# Solarduino.net
KiCad netlist of a schematic drawn in EAGLE
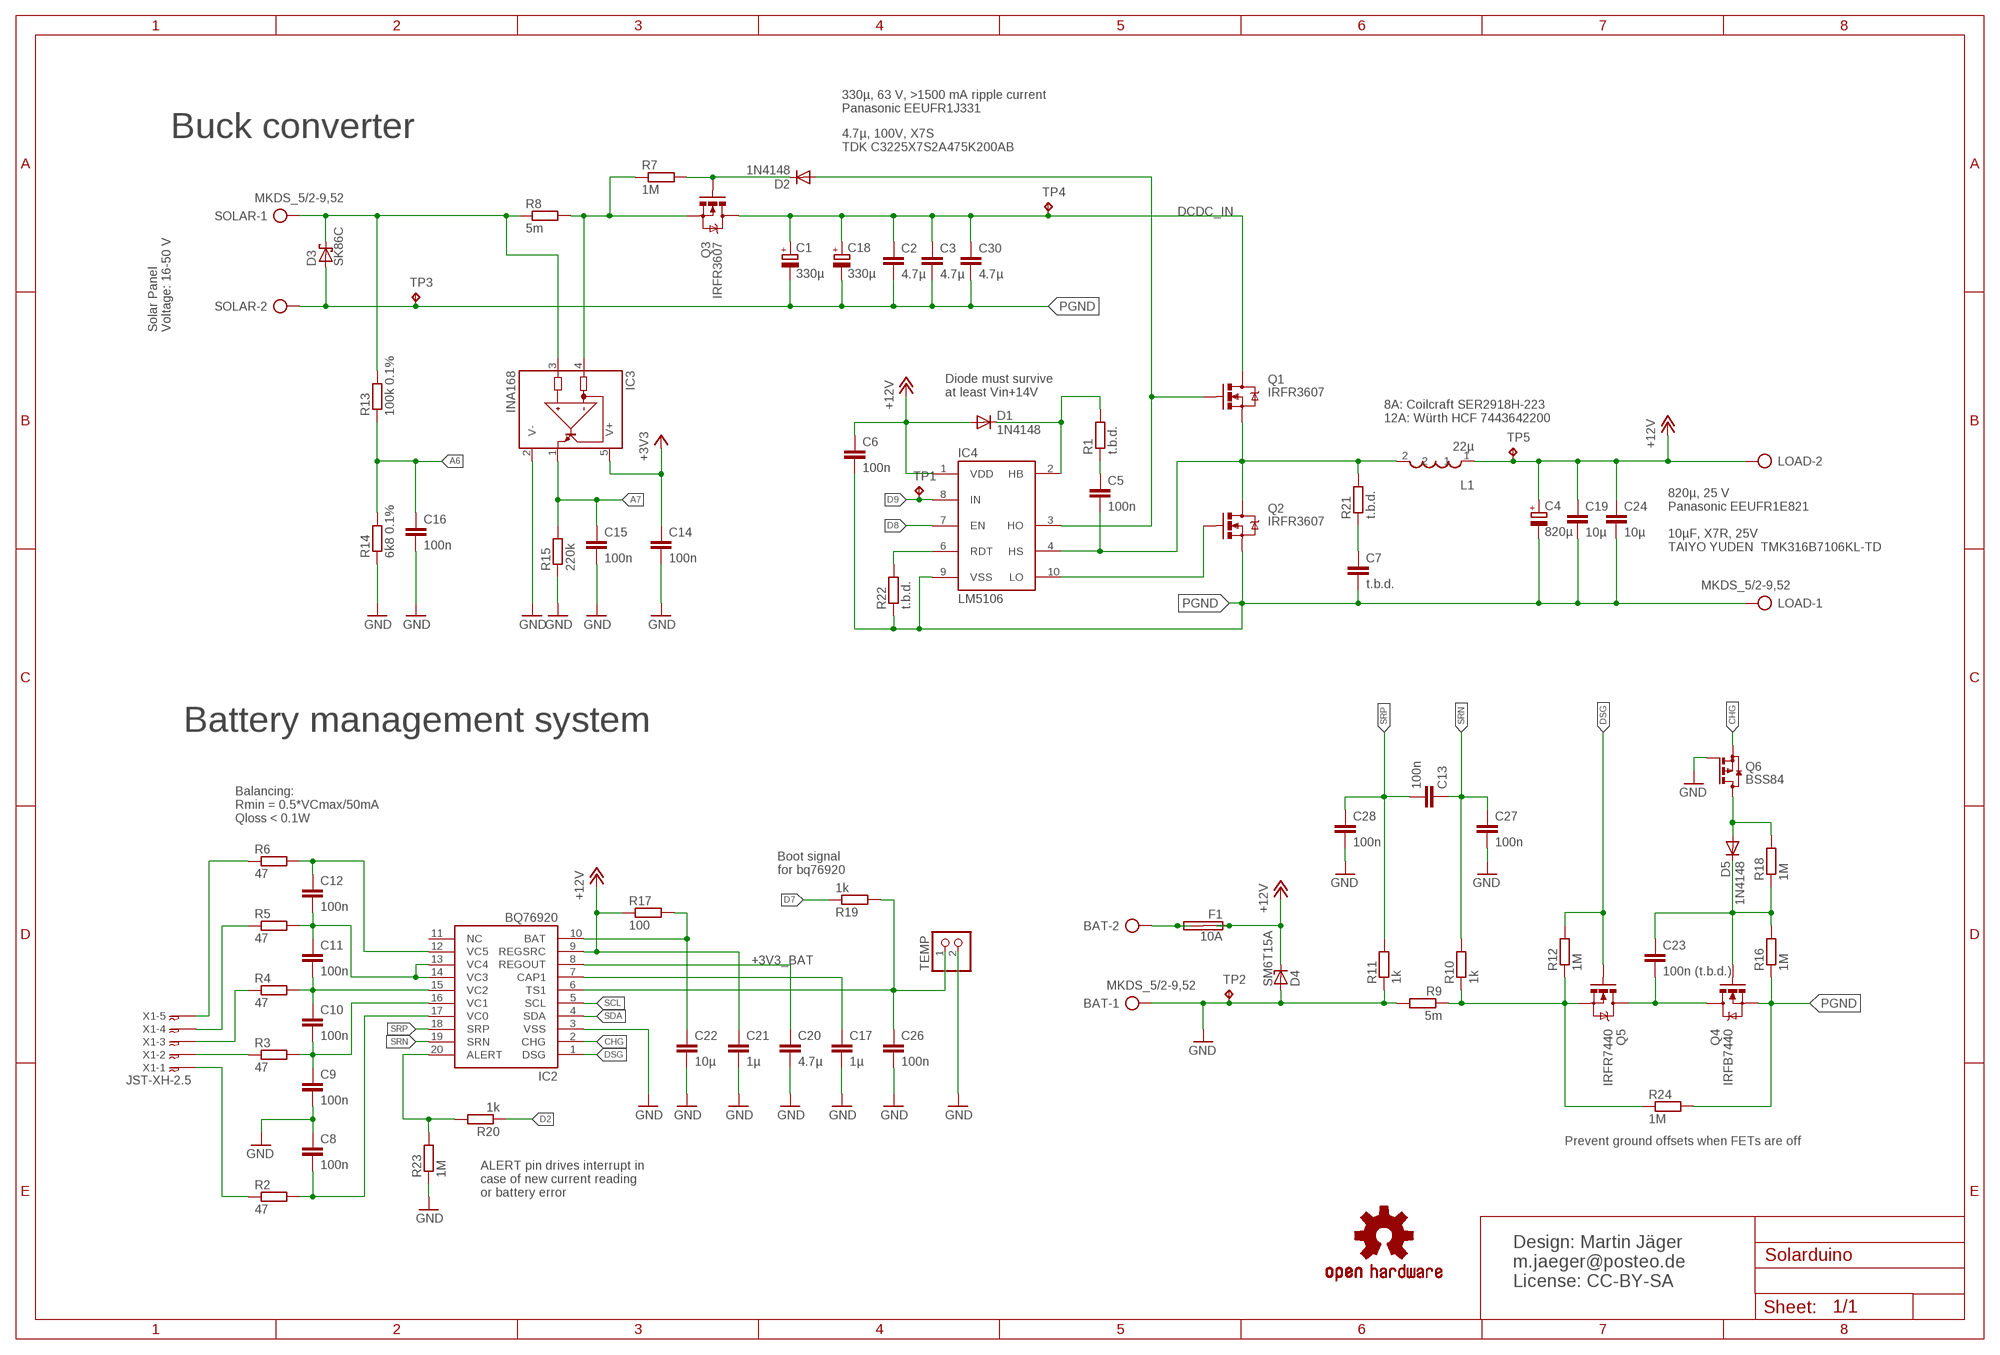
[diagram p0: schematic, sheet 1, part 1 of 2]
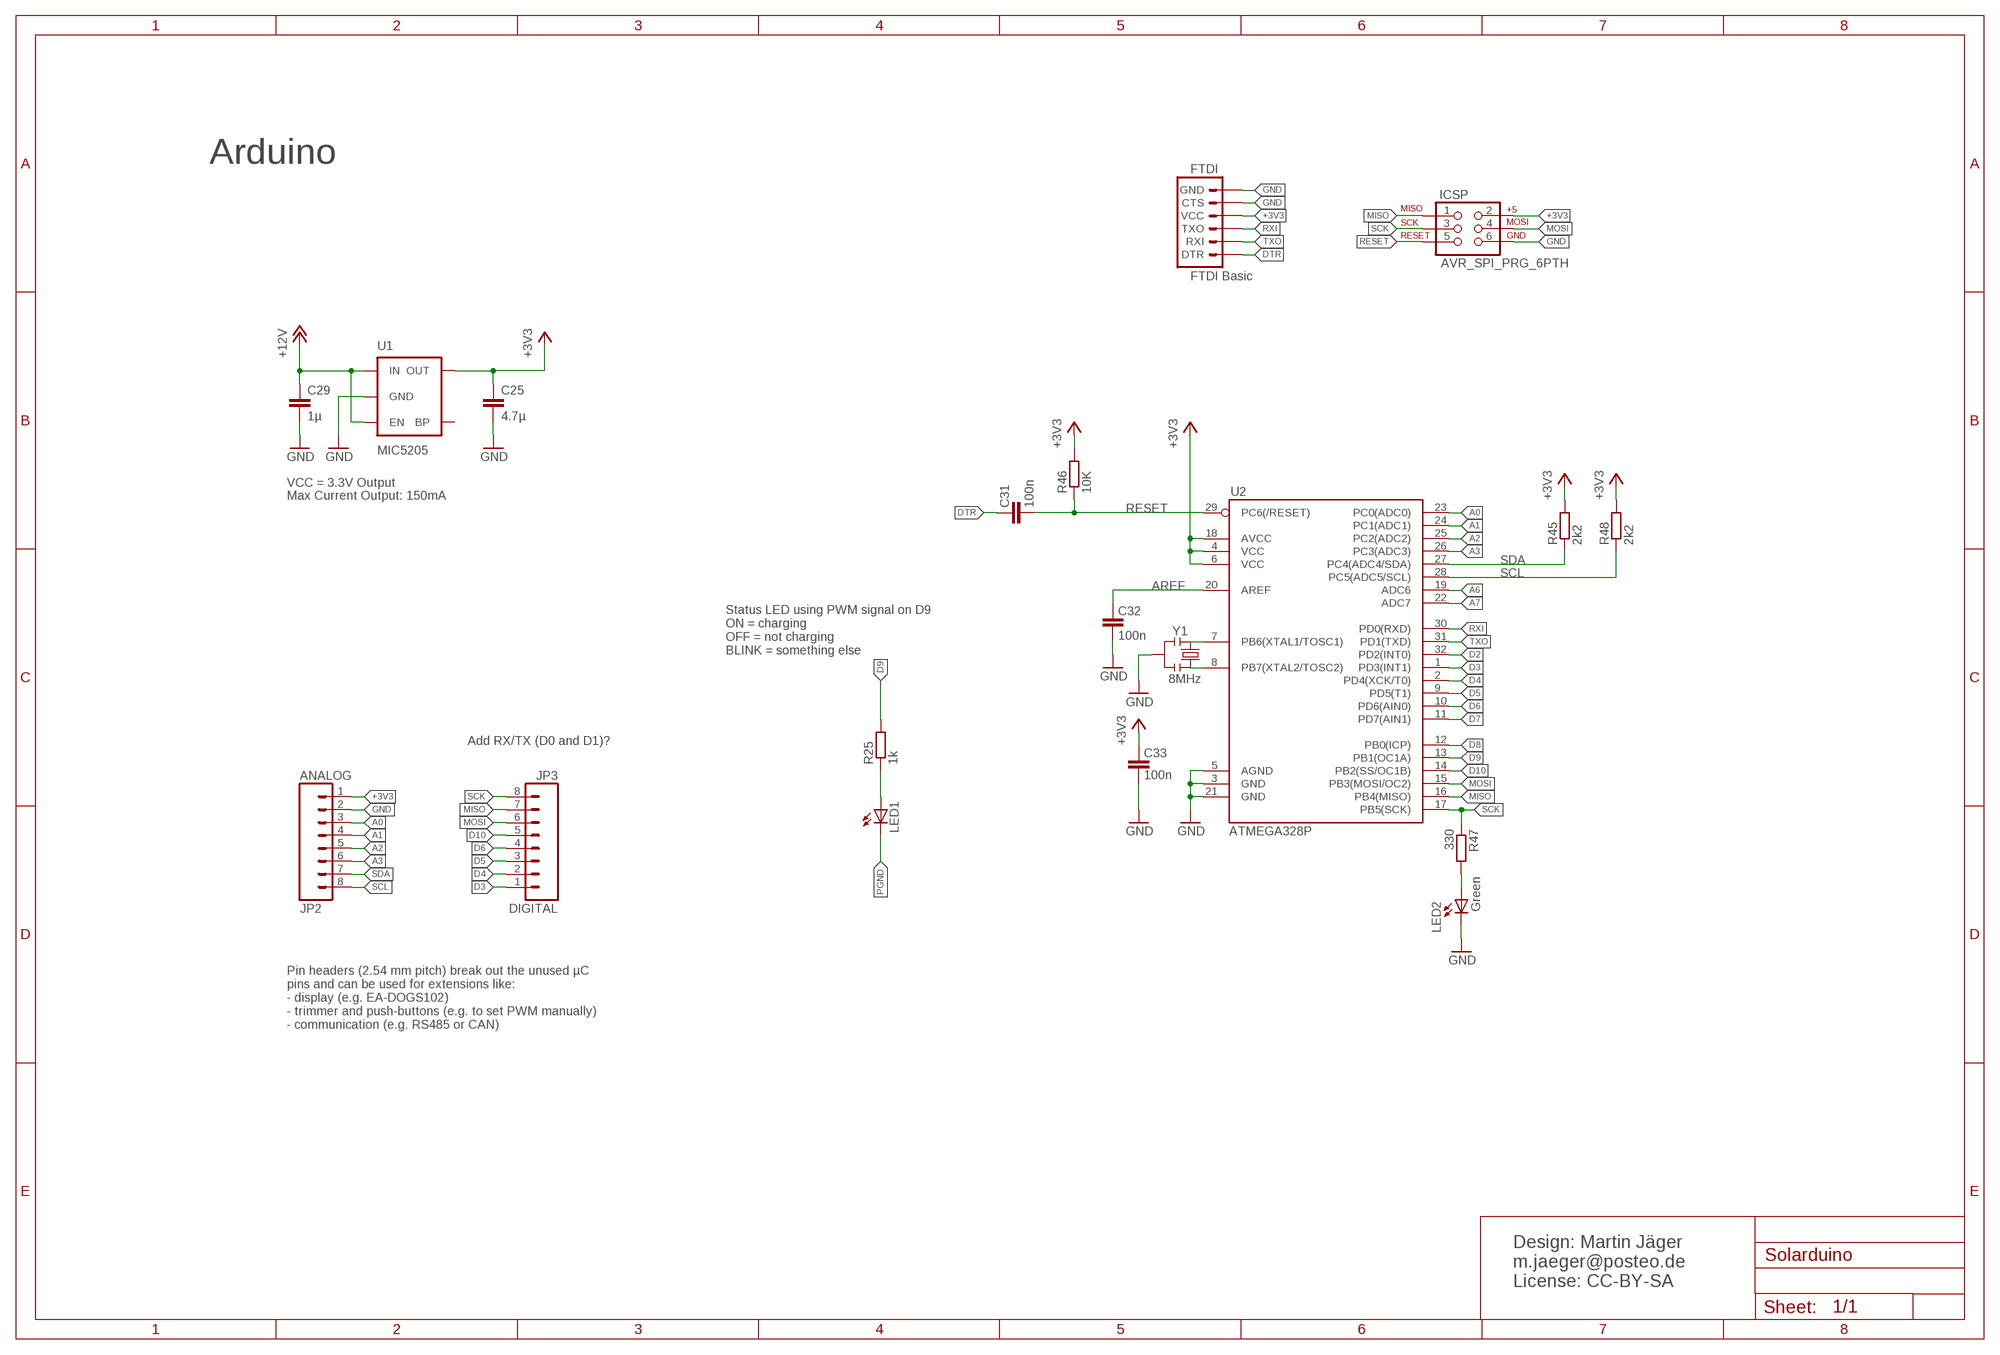
[diagram p1: schematic, sheet 1, part 2 of 2]

(export (version "E")
  (design (tool "Eeschema 10.0.6"))
  (components
    (comp (ref "BAT")
      (value "MKDS_5/2-9,52")
      (footprint "eagle-import:MKDS_5_2-952")
      (fields (field (name "OC_FARNELL") "unknown"))
      (libsource (lib "eagle-import") (part "MKDS_5/2-9,52"))
    )
    (comp (ref "C1")
      (value "330µ")
      (footprint "eagle-import:E5-13")
      (fields (field (name "MF") "PANASONIC ELECTRONIC COMPONENTS") (field (name "MPN") "EEUFR1J331B"))
      (libsource (lib "eagle-import") (part "CPOL-EUE5-13"))
    )
    (comp (ref "C2")
      (value "4.7µ")
      (footprint "eagle-import:C1210")
      (fields (field (name "MF") "TDK") (field (name "MPN") "C3225X7S2A475K200AB"))
      (libsource (lib "eagle-import") (part "C-EUC1210"))
    )
    (comp (ref "C3")
      (value "4.7µ")
      (footprint "eagle-import:C1210")
      (fields (field (name "MF") "TDK") (field (name "MPN") "C3225X7S2A475K200AB"))
      (libsource (lib "eagle-import") (part "C-EUC1210"))
    )
    (comp (ref "C4")
      (value "820µ")
      (footprint "eagle-import:E5-10,5")
      (fields (field (name "MF") "PANASONIC ELECTRONIC COMPONENTS") (field (name "MPN") "EEUFR1E821B"))
      (libsource (lib "eagle-import") (part "CPOL-EUE5-10.5"))
    )
    (comp (ref "C5")
      (value "100n")
      (footprint "eagle-import:C0805")
      (fields (field (name "MF") "AVX") (field (name "MPN") "08055C104KAT2A"))
      (libsource (lib "eagle-import") (part "C-EUC0805"))
    )
    (comp (ref "C6")
      (value "100n")
      (footprint "eagle-import:C0805")
      (fields (field (name "MF") "AVX") (field (name "MPN") "08055C104KAT2A"))
      (libsource (lib "eagle-import") (part "C-EUC0805"))
    )
    (comp (ref "C7")
      (value "t.b.d.")
      (footprint "eagle-import:C0805")
      (fields (field (name "MF") "AVX") (field (name "MPN") "08055C104KAT2A"))
      (libsource (lib "eagle-import") (part "C-EUC0805"))
    )
    (comp (ref "C8")
      (value "100n")
      (footprint "eagle-import:C0805")
      (fields (field (name "MF") "AVX") (field (name "MPN") "08055C104KAT2A"))
      (libsource (lib "eagle-import") (part "C-EUC0805"))
    )
    (comp (ref "C9")
      (value "100n")
      (footprint "eagle-import:C0805")
      (fields (field (name "MF") "AVX") (field (name "MPN") "08055C104KAT2A"))
      (libsource (lib "eagle-import") (part "C-EUC0805"))
    )
    (comp (ref "C10")
      (value "100n")
      (footprint "eagle-import:C0805")
      (fields (field (name "MF") "AVX") (field (name "MPN") "08055C104KAT2A"))
      (libsource (lib "eagle-import") (part "C-EUC0805"))
    )
    (comp (ref "C11")
      (value "100n")
      (footprint "eagle-import:C0805")
      (fields (field (name "MF") "AVX") (field (name "MPN") "08055C104KAT2A"))
      (libsource (lib "eagle-import") (part "C-EUC0805"))
    )
    (comp (ref "C12")
      (value "100n")
      (footprint "eagle-import:C0805")
      (fields (field (name "MF") "AVX") (field (name "MPN") "08055C104KAT2A"))
      (libsource (lib "eagle-import") (part "C-EUC0805"))
    )
    (comp (ref "C13")
      (value "100n")
      (footprint "eagle-import:C0805")
      (fields (field (name "MF") "AVX") (field (name "MPN") "08055C104KAT2A"))
      (libsource (lib "eagle-import") (part "C-EUC0805"))
    )
    (comp (ref "C14")
      (value "100n")
      (footprint "eagle-import:C0805")
      (fields (field (name "MF") "AVX") (field (name "MPN") "08055C104KAT2A"))
      (libsource (lib "eagle-import") (part "C-EUC0805"))
    )
    (comp (ref "C15")
      (value "100n")
      (footprint "eagle-import:C0805")
      (fields (field (name "MF") "AVX") (field (name "MPN") "08055C104KAT2A"))
      (libsource (lib "eagle-import") (part "C-EUC0805"))
    )
    (comp (ref "C16")
      (value "100n")
      (footprint "eagle-import:C0805")
      (fields (field (name "MF") "AVX") (field (name "MPN") "08055C104KAT2A"))
      (libsource (lib "eagle-import") (part "C-EUC0805"))
    )
    (comp (ref "C17")
      (value "1µ")
      (footprint "eagle-import:C0805")
      (fields (field (name "MF") "AVX") (field (name "MPN") "08053C105KAT2A"))
      (libsource (lib "eagle-import") (part "C-EUC0805"))
    )
    (comp (ref "C18")
      (value "330µ")
      (footprint "eagle-import:E5-13")
      (fields (field (name "MF") "PANASONIC ELECTRONIC COMPONENTS") (field (name "MPN") "EEUFR1J331B"))
      (libsource (lib "eagle-import") (part "CPOL-EUE5-13"))
    )
    (comp (ref "C19")
      (value "10µ")
      (footprint "eagle-import:C1206")
      (fields (field (name "MF") "TAIYO YUDEN") (field (name "MPN") "TMK316B7106KL-TD"))
      (libsource (lib "eagle-import") (part "C-EUC1206"))
    )
    (comp (ref "C20")
      (value "4.7µ")
      (footprint "eagle-import:C0805")
      (fields (field (name "MF") "AVX") (field (name "MPN") "0805YC475KAT2A"))
      (libsource (lib "eagle-import") (part "C-EUC0805"))
    )
    (comp (ref "C21")
      (value "1µ")
      (footprint "eagle-import:C0805")
      (fields (field (name "MF") "AVX") (field (name "MPN") "08053C105KAT2A"))
      (libsource (lib "eagle-import") (part "C-EUC0805"))
    )
    (comp (ref "C22")
      (value "10µ")
      (footprint "eagle-import:C1206")
      (fields (field (name "MF") "TAIYO YUDEN") (field (name "MPN") "TMK316B7106KL-TD"))
      (libsource (lib "eagle-import") (part "C-EUC1206"))
    )
    (comp (ref "C23")
      (value "100n (t.b.d.)")
      (footprint "eagle-import:C0805")
      (fields (field (name "MF") "AVX") (field (name "MPN") "08055C104KAT2A"))
      (libsource (lib "eagle-import") (part "C-EUC0805"))
    )
    (comp (ref "C24")
      (value "10µ")
      (footprint "eagle-import:C1206")
      (fields (field (name "MF") "TAIYO YUDEN") (field (name "MPN") "TMK316B7106KL-TD"))
      (libsource (lib "eagle-import") (part "C-EUC1206"))
    )
    (comp (ref "C25")
      (value "4.7µ")
      (footprint "eagle-import:C0805")
      (fields (field (name "MF") "AVX") (field (name "MPN") "0805YC475KAT2A"))
      (libsource (lib "eagle-import") (part "C-EUC0805"))
    )
    (comp (ref "C26")
      (value "100n")
      (footprint "eagle-import:C0805")
      (fields (field (name "MF") "AVX") (field (name "MPN") "08055C104KAT2A"))
      (libsource (lib "eagle-import") (part "C-EUC0805"))
    )
    (comp (ref "C27")
      (value "100n")
      (footprint "eagle-import:C0805")
      (fields (field (name "MF") "AVX") (field (name "MPN") "08055C104KAT2A"))
      (libsource (lib "eagle-import") (part "C-EUC0805"))
    )
    (comp (ref "C28")
      (value "100n")
      (footprint "eagle-import:C0805")
      (fields (field (name "MF") "AVX") (field (name "MPN") "08055C104KAT2A"))
      (libsource (lib "eagle-import") (part "C-EUC0805"))
    )
    (comp (ref "C29")
      (value "1µ")
      (footprint "eagle-import:C0805")
      (fields (field (name "MF") "AVX") (field (name "MPN") "08053C105KAT2A"))
      (libsource (lib "eagle-import") (part "C-EUC0805"))
    )
    (comp (ref "C30")
      (value "4.7µ")
      (footprint "eagle-import:C1210")
      (fields (field (name "MF") "TDK") (field (name "MPN") "C3225X7S2A475K200AB"))
      (libsource (lib "eagle-import") (part "C-EUC1210"))
    )
    (comp (ref "C31")
      (value "100n")
      (footprint "eagle-import:C0805")
      (fields (field (name "MF") "AVX") (field (name "MPN") "08055C104KAT2A"))
      (libsource (lib "eagle-import") (part "C-EUC0805"))
    )
    (comp (ref "C32")
      (value "100n")
      (footprint "eagle-import:C0805")
      (fields (field (name "MF") "AVX") (field (name "MPN") "08055C104KAT2A"))
      (libsource (lib "eagle-import") (part "C-EUC0805"))
    )
    (comp (ref "C33")
      (value "100n")
      (footprint "eagle-import:C0805")
      (fields (field (name "MF") "AVX") (field (name "MPN") "08055C104JAT2A"))
      (libsource (lib "eagle-import") (part "C-EUC0805"))
    )
    (comp (ref "D1")
      (value "1N4148")
      (footprint "eagle-import:SOD323-R")
      (fields (field (name "MF") "VISHAY SEMICONDUCTOR") (field (name "MPN") "1N4148WS-E3-08"))
      (libsource (lib "eagle-import") (part "DIODE-SOD323-R"))
    )
    (comp (ref "D2")
      (value "1N4148")
      (footprint "eagle-import:SOD323-R")
      (fields (field (name "MF") "VISHAY SEMICONDUCTOR") (field (name "MPN") "1N4148WS-E3-08"))
      (libsource (lib "eagle-import") (part "DIODE-SOD323-R"))
    )
    (comp (ref "D3")
      (value "SK86C")
      (footprint "eagle-import:SMC")
      (fields (field (name "MF") "TAIWAN SEMICONDUCTOR") (field (name "MPN") "SK56C"))
      (libsource (lib "eagle-import") (part "SCHOTTKY-DIODESMC"))
    )
    (comp (ref "D4")
      (value "SM6T15A")
      (footprint "eagle-import:SMB")
      (fields (field (name "MF") "MULTICOMP") (field (name "MPN") "P6SMBJ15A"))
      (libsource (lib "eagle-import") (part "ZENER-DIODESMB"))
    )
    (comp (ref "D5")
      (value "1N4148")
      (footprint "eagle-import:SOD323-R")
      (fields (field (name "MF") "VISHAY SEMICONDUCTOR") (field (name "MPN") "1N4148WS-E3-08"))
      (libsource (lib "eagle-import") (part "DIODE-SOD323-R"))
    )
    (comp (ref "F1")
      (value "10A")
      (footprint "eagle-import:SHK20Q")
      (libsource (lib "eagle-import") (part "SHK20Q"))
    )
    (comp (ref "FTDI")
      (value "FTDI Basic")
      (footprint "eagle-import:1X06")
      (fields (field (name "MF") "MULTICOMP") (field (name "MPN") "2212S-06SG-85"))
      (libsource (lib "eagle-import") (part "ARDUINO_SERIAL_PROGRAMPTH"))
    )
    (comp (ref "IC2")
      (value "BQ76920")
      (footprint "eagle-import:TSSOP20")
      (libsource (lib "eagle-import") (part "BQ76920"))
    )
    (comp (ref "IC3")
      (value "INA168")
      (footprint "eagle-import:SOT23-5")
      (fields
        (field (name "MF") "TEXAS INSTRUMENTS")
        (field (name "MPN") "INA168NA/250")
        (field (name "MPN_1") "INA168NA/250.")
      )
      (libsource (lib "eagle-import") (part "INA168"))
    )
    (comp (ref "IC4")
      (value "LM5106")
      (footprint "eagle-import:VSSOP10")
      (fields (field (name "MF") "TEXAS INSTRUMENTS") (field (name "MPN") "LM5106MM/NOPB"))
      (libsource (lib "eagle-import") (part "LM5106"))
    )
    (comp (ref "ICSP")
      (value "AVR_SPI_PRG_6PTH")
      (footprint "eagle-import:2X3")
      (libsource (lib "eagle-import") (part "AVR_SPI_PRG_6PTH"))
    )
    (comp (ref "JP2")
      (value "ANALOG")
      (footprint "eagle-import:1X08_ROUND")
      (libsource (lib "eagle-import") (part "M08"))
    )
    (comp (ref "JP3")
      (value "DIGITAL")
      (footprint "eagle-import:1X08_ROUND")
      (libsource (lib "eagle-import") (part "M08"))
    )
    (comp (ref "L1")
      (value "22µ")
      (footprint "eagle-import:WE-HCF_2818_7443643300")
      (fields (field (name "MF") "COILCRAFT") (field (name "MPN") "SER2918H-223KL"))
      (libsource (lib "eagle-import") (part "WE-HCF_2818_7443643300"))
    )
    (comp (ref "LED1")
      (value "LED3MM")
      (footprint "eagle-import:LED3MM")
      (fields (field (name "MF") "MULTICOMP") (field (name "MPN") "MCL034GD"))
      (libsource (lib "eagle-import") (part "led_LED3MM"))
    )
    (comp (ref "LED2")
      (value "Green")
      (footprint "eagle-import:0603-LED-ALT1")
      (fields (field (name "MF") "MULTICOMP") (field (name "MPN") "MCL034GD"))
      (libsource (lib "eagle-import") (part "LED"))
    )
    (comp (ref "LOAD")
      (value "MKDS_5/2-9,52")
      (footprint "eagle-import:MKDS_5_2-952")
      (fields (field (name "OC_FARNELL") "unknown"))
      (libsource (lib "eagle-import") (part "MKDS_5/2-9,52"))
    )
    (comp (ref "N1")
      (value "OSHW-LOGOM")
      (footprint "eagle-import:OSHW-LOGO-M")
      (libsource (lib "eagle-import") (part "OSHW-LOGOM"))
    )
    (comp (ref "Q1")
      (value "IRFR3607")
      (footprint "eagle-import:DPAK")
      (fields (field (name "MF") "INTERNATIONAL RECTIFIER") (field (name "MPN") "IRFR3607PBF"))
      (libsource (lib "eagle-import") (part "MOSFET-NCHANNELFDD8780"))
    )
    (comp (ref "Q2")
      (value "IRFR3607")
      (footprint "eagle-import:DPAK")
      (fields (field (name "MF") "INTERNATIONAL RECTIFIER") (field (name "MPN") "IRFR3607PBF"))
      (libsource (lib "eagle-import") (part "MOSFET-NCHANNELFDD8780"))
    )
    (comp (ref "Q3")
      (value "IRFR3607")
      (footprint "eagle-import:DPAK")
      (fields (field (name "MF") "INTERNATIONAL RECTIFIER") (field (name "MPN") "IRFR3607PBF"))
      (libsource (lib "eagle-import") (part "MOSFET-NCHANNELFDD8780"))
    )
    (comp (ref "Q4")
      (value "IRFB7440")
      (footprint "eagle-import:DPAK")
      (fields (field (name "MF") "INTERNATIONAL RECTIFIER") (field (name "MPN") "IRFR7440TRPBF"))
      (libsource (lib "eagle-import") (part "MOSFET-NCHANNELFDD8780"))
    )
    (comp (ref "Q5")
      (value "IRFR7440")
      (footprint "eagle-import:DPAK")
      (fields (field (name "MF") "INTERNATIONAL RECTIFIER") (field (name "MPN") "IRFR7440TRPBF"))
      (libsource (lib "eagle-import") (part "MOSFET-NCHANNELFDD8780"))
    )
    (comp (ref "Q6")
      (value "BSS84")
      (footprint "eagle-import:SOT23")
      (fields (field (name "MF") "MULTICOMP") (field (name "MPN") "BSS84-7-F"))
      (libsource (lib "eagle-import") (part "BSS84"))
    )
    (comp (ref "R1")
      (value "t.b.d.")
      (footprint "eagle-import:R0805")
      (fields (field (name "MF") "BOURNS") (field (name "MPN") "CR0805-FX-1001ELF"))
      (libsource (lib "eagle-import") (part "R-EU_R0805"))
    )
    (comp (ref "R2")
      (value "47")
      (footprint "eagle-import:R2512")
      (fields (field (name "MF") "MULTICOMP") (field (name "MPN") "MCHP122WF470JT4E"))
      (libsource (lib "eagle-import") (part "R-EU_R2512"))
    )
    (comp (ref "R3")
      (value "47")
      (footprint "eagle-import:R2512")
      (fields (field (name "MF") "MULTICOMP") (field (name "MPN") "MCHP122WF470JT4E"))
      (libsource (lib "eagle-import") (part "R-EU_R2512"))
    )
    (comp (ref "R4")
      (value "47")
      (footprint "eagle-import:R2512")
      (fields (field (name "MF") "MULTICOMP") (field (name "MPN") "MCHP122WF470JT4E"))
      (libsource (lib "eagle-import") (part "R-EU_R2512"))
    )
    (comp (ref "R5")
      (value "47")
      (footprint "eagle-import:R2512")
      (fields (field (name "MF") "MULTICOMP") (field (name "MPN") "MCHP122WF470JT4E"))
      (libsource (lib "eagle-import") (part "R-EU_R2512"))
    )
    (comp (ref "R6")
      (value "47")
      (footprint "eagle-import:R2512")
      (fields (field (name "MF") "MULTICOMP") (field (name "MPN") "MCHP122WF470JT4E"))
      (libsource (lib "eagle-import") (part "R-EU_R2512"))
    )
    (comp (ref "R7")
      (value "1M")
      (footprint "eagle-import:R0805")
      (fields (field (name "MF") "BOURNS") (field (name "MPN") "CR0805-FX-1004ELF."))
      (libsource (lib "eagle-import") (part "R-EU_R0805"))
    )
    (comp (ref "R8")
      (value "5m")
      (footprint "eagle-import:R2512")
      (fields (field (name "MF") "BOURNS") (field (name "MPN") "CRF2512-FX-R005ELF"))
      (libsource (lib "eagle-import") (part "R-EU_R2512"))
    )
    (comp (ref "R9")
      (value "5m")
      (footprint "eagle-import:R2512")
      (fields (field (name "MF") "BOURNS") (field (name "MPN") "CRF2512-FX-R005ELF"))
      (libsource (lib "eagle-import") (part "R-EU_R2512"))
    )
    (comp (ref "R10")
      (value "1k")
      (footprint "eagle-import:R0805")
      (fields (field (name "MF") "BOURNS") (field (name "MPN") "CR0805-FX-1001ELF"))
      (libsource (lib "eagle-import") (part "R-EU_R0805"))
    )
    (comp (ref "R11")
      (value "1k")
      (footprint "eagle-import:R0805")
      (fields (field (name "MF") "BOURNS") (field (name "MPN") "CR0805-FX-1001ELF"))
      (libsource (lib "eagle-import") (part "R-EU_R0805"))
    )
    (comp (ref "R12")
      (value "1M")
      (footprint "eagle-import:R0805")
      (fields (field (name "MF") "BOURNS") (field (name "MPN") "CR0805-FX-1004ELF."))
      (libsource (lib "eagle-import") (part "R-EU_R0805"))
    )
    (comp (ref "R13")
      (value "100k 0.1%")
      (footprint "eagle-import:R0805")
      (fields (field (name "MF") "PANASONIC ELECTRONIC COMPONENTS") (field (name "MPN") "ERA6AEB104V"))
      (libsource (lib "eagle-import") (part "R-EU_R0805"))
    )
    (comp (ref "R14")
      (value "6k8 0.1%")
      (footprint "eagle-import:R0805")
      (fields (field (name "MF") "PANASONIC ELECTRONIC COMPONENTS") (field (name "MPN") "ERA6AEB682V"))
      (libsource (lib "eagle-import") (part "R-EU_R0805"))
    )
    (comp (ref "R15")
      (value "220k")
      (footprint "eagle-import:R0805")
      (fields (field (name "MF") "BOURNS") (field (name "MPN") "CHV0805-FX-2203ELF"))
      (libsource (lib "eagle-import") (part "R-EU_R0805"))
    )
    (comp (ref "R16")
      (value "1M")
      (footprint "eagle-import:R0805")
      (fields (field (name "MF") "BOURNS") (field (name "MPN") "CR0805-FX-1004ELF."))
      (libsource (lib "eagle-import") (part "R-EU_R0805"))
    )
    (comp (ref "R17")
      (value "100")
      (footprint "eagle-import:R0805")
      (fields (field (name "MF") "BOURNS") (field (name "MPN") "CR0805-FX-1000-ELF"))
      (libsource (lib "eagle-import") (part "R-EU_R0805"))
    )
    (comp (ref "R18")
      (value "1M")
      (footprint "eagle-import:R0805")
      (fields (field (name "MF") "BOURNS") (field (name "MPN") "CR0805-FX-1004ELF."))
      (libsource (lib "eagle-import") (part "R-EU_R0805"))
    )
    (comp (ref "R19")
      (value "1k")
      (footprint "eagle-import:R0805")
      (fields (field (name "MF") "BOURNS") (field (name "MPN") "CR0805-FX-1001ELF"))
      (libsource (lib "eagle-import") (part "R-EU_R0805"))
    )
    (comp (ref "R20")
      (value "1k")
      (footprint "eagle-import:R0805")
      (fields (field (name "MF") "BOURNS") (field (name "MPN") "CR0805-FX-1001ELF"))
      (libsource (lib "eagle-import") (part "R-EU_R0805"))
    )
    (comp (ref "R21")
      (value "t.b.d.")
      (footprint "eagle-import:R2010")
      (fields (field (name "MF") "BOURNS") (field (name "MPN") "CRM2010-JW-2R2ELF"))
      (libsource (lib "eagle-import") (part "R-EU_R2010"))
    )
    (comp (ref "R22")
      (value "t.b.d.")
      (footprint "eagle-import:R0805")
      (fields (field (name "MF") "BOURNS") (field (name "MPN") "CR0805-FX-1001ELF"))
      (libsource (lib "eagle-import") (part "R-EU_R0805"))
    )
    (comp (ref "R23")
      (value "1M")
      (footprint "eagle-import:R0805")
      (fields (field (name "MF") "BOURNS") (field (name "MPN") "CR0805-FX-1004ELF."))
      (libsource (lib "eagle-import") (part "R-EU_R0805"))
    )
    (comp (ref "R24")
      (value "1M")
      (footprint "eagle-import:R0805")
      (fields (field (name "MF") "BOURNS") (field (name "MPN") "CR0805-FX-1004ELF."))
      (libsource (lib "eagle-import") (part "R-EU_R0805"))
    )
    (comp (ref "R25")
      (value "1k")
      (footprint "eagle-import:R0805")
      (fields (field (name "MF") "BOURNS") (field (name "MPN") "CR0805-FX-1001ELF"))
      (libsource (lib "eagle-import") (part "R-EU_R0805"))
    )
    (comp (ref "R45")
      (value "2k2")
      (footprint "eagle-import:R0805")
      (fields (field (name "MF") "BOURNS") (field (name "MPN") "CR0805-FX-1001ELF"))
      (libsource (lib "eagle-import") (part "R-EU_R0805"))
    )
    (comp (ref "R46")
      (value "10K")
      (footprint "eagle-import:R0805")
      (fields (field (name "MF") "BOURNS") (field (name "MPN") "CR0805-FX-1002ELF"))
      (libsource (lib "eagle-import") (part "R-EU_R0805"))
    )
    (comp (ref "R47")
      (value "330")
      (footprint "eagle-import:R0805")
      (fields (field (name "MF") "BOURNS") (field (name "MPN") "CR0805-FX-3300ELF"))
      (libsource (lib "eagle-import") (part "R-EU_R0805"))
    )
    (comp (ref "R48")
      (value "2k2")
      (footprint "eagle-import:R0805")
      (fields (field (name "MF") "BOURNS") (field (name "MPN") "CR0805-FX-1001ELF"))
      (libsource (lib "eagle-import") (part "R-EU_R0805"))
    )
    (comp (ref "SOLAR")
      (value "MKDS_5/2-9,52")
      (footprint "eagle-import:MKDS_5_2-952")
      (fields (field (name "OC_FARNELL") "unknown"))
      (libsource (lib "eagle-import") (part "MKDS_5/2-9,52"))
    )
    (comp (ref "TEMP")
      (value "PINHD-1X2/90")
      (footprint "eagle-import:1X02_90")
      (fields (field (name "MF") "MULTICOMP") (field (name "MPN") "MC34745"))
      (libsource (lib "eagle-import") (part "PINHD-1X2/90"))
    )
    (comp (ref "TP1")
      (value "TPPAD1-13")
      (footprint "eagle-import:P1-13")
      (libsource (lib "eagle-import") (part "TPPAD1-13"))
    )
    (comp (ref "TP2")
      (value "TPPAD1-13")
      (footprint "eagle-import:P1-13")
      (libsource (lib "eagle-import") (part "TPPAD1-13"))
    )
    (comp (ref "TP3")
      (value "TPPAD1-13")
      (footprint "eagle-import:P1-13")
      (libsource (lib "eagle-import") (part "TPPAD1-13"))
    )
    (comp (ref "TP4")
      (value "TPPAD1-13")
      (footprint "eagle-import:P1-13")
      (libsource (lib "eagle-import") (part "TPPAD1-13"))
    )
    (comp (ref "TP5")
      (value "TPPAD1-13")
      (footprint "eagle-import:P1-13")
      (libsource (lib "eagle-import") (part "TPPAD1-13"))
    )
    (comp (ref "U1")
      (value "MIC5205")
      (footprint "eagle-import:SOT23-5")
      (fields (field (name "MF") "MICREL SEMICONDUCTOR") (field (name "MPN") "MIC5205-3.3YM5 TR"))
      (libsource (lib "eagle-import") (part "V_REG_LDOSMD"))
    )
    (comp (ref "U2")
      (value "ATMEGA328P")
      (footprint "eagle-import:TQFP32-08")
      (fields (field (name "MF") "ATMEL") (field (name "MPN") "ATMEGA328P-AU"))
      (libsource (lib "eagle-import") (part "ATMEGA168"))
    )
    (comp (ref "X1")
      (value "JST-XH-2.5")
      (footprint "eagle-import:S5B-XH")
      (fields
        (field (name "MF") "JST (JAPAN SOLDERLESS TERMINALS)")
        (field (name "MPN") "S5B-XH-A (LF)(SN)")
        (field (name "OC_FARNELL") "1516293")
      )
      (libsource (lib "eagle-import") (part "05-JST-S5B-XH-A"))
    )
    (comp (ref "Y1")
      (value "8MHz")
      (footprint "eagle-import:RESONATOR-SMD")
      (fields (field (name "MF") "MURATA") (field (name "MPN") "CSTCE8M00G55-R0"))
      (libsource (lib "eagle-import") (part "RESONATORSMD"))
    )
  )
  (nets
    (net (code "1") (name "+3V3") (class "Default")
      (node (ref "C14") (pin "1") (pinfunction "1_1") (pintype "passive"))
      (node (ref "C25") (pin "1") (pinfunction "1_1") (pintype "passive"))
      (node (ref "C33") (pin "2") (pinfunction "2_2") (pintype "passive"))
      (node (ref "FTDI") (pin "4") (pinfunction "VCC_4") (pintype "passive"))
      (node (ref "IC3") (pin "5") (pinfunction "V+_5") (pintype "power_in"))
      (node (ref "ICSP") (pin "2") (pinfunction "2_2") (pintype "passive"))
      (node (ref "JP2") (pin "1") (pinfunction "1_1") (pintype "passive"))
      (node (ref "R45") (pin "2") (pinfunction "2_2") (pintype "passive"))
      (node (ref "R46") (pin "2") (pinfunction "2_2") (pintype "passive"))
      (node (ref "R48") (pin "2") (pinfunction "2_2") (pintype "passive"))
      (node (ref "U1") (pin "5") (pinfunction "OUT_5") (pintype "passive"))
      (node (ref "U2") (pin "18") (pinfunction "AVCC_18") (pintype "bidirectional"))
      (node (ref "U2") (pin "4") (pinfunction "VCC_4") (pintype "bidirectional"))
      (node (ref "U2") (pin "6") (pinfunction "VCC_6") (pintype "bidirectional"))
    )
    (net (code "2") (name "+12V") (class "Default")
      (node (ref "C19") (pin "1") (pinfunction "1_1") (pintype "passive"))
      (node (ref "C21") (pin "1") (pinfunction "1_1") (pintype "passive"))
      (node (ref "C24") (pin "1") (pinfunction "1_1") (pintype "passive"))
      (node (ref "C29") (pin "1") (pinfunction "1_1") (pintype "passive"))
      (node (ref "C4") (pin "+") (pinfunction "+_+") (pintype "passive"))
      (node (ref "C6") (pin "1") (pinfunction "1_1") (pintype "passive"))
      (node (ref "D1") (pin "A") (pinfunction "A_A") (pintype "passive"))
      (node (ref "D4") (pin "C") (pinfunction "C_C") (pintype "passive"))
      (node (ref "F1") (pin "1A") (pinfunction "1A_1A") (pintype "passive"))
      (node (ref "F1") (pin "1B") (pinfunction "1B_1B") (pintype "passive"))
      (node (ref "IC2") (pin "9") (pinfunction "REGSRC_9") (pintype "input"))
      (node (ref "IC4") (pin "1") (pinfunction "VDD_1") (pintype "power_in"))
      (node (ref "L1") (pin "1") (pinfunction "1_1") (pintype "bidirectional"))
      (node (ref "LOAD") (pin "2") (pinfunction "KL_2") (pintype "passive"))
      (node (ref "R17") (pin "1") (pinfunction "1_1") (pintype "passive"))
      (node (ref "TP5") (pin "TP") (pinfunction "TP_TP") (pintype "input"))
      (node (ref "U1") (pin "1") (pinfunction "IN_1") (pintype "input"))
      (node (ref "U1") (pin "3") (pinfunction "EN_3") (pintype "input"))
    )
    (net (code "3") (name "/+3V3_BAT") (class "Default")
      (node (ref "C20") (pin "1") (pinfunction "1_1") (pintype "passive"))
      (node (ref "IC2") (pin "8") (pinfunction "REGOUT_8") (pintype "power_in"))
    )
    (net (code "4") (name "/AREF") (class "Default")
      (node (ref "C32") (pin "2") (pinfunction "2_2") (pintype "passive"))
      (node (ref "U2") (pin "20") (pinfunction "AREF_20") (pintype "bidirectional"))
    )
    (net (code "5") (name "/DCDC_IN") (class "Default")
      (node (ref "C1") (pin "+") (pinfunction "+_+") (pintype "passive"))
      (node (ref "C18") (pin "+") (pinfunction "+_+") (pintype "passive"))
      (node (ref "C2") (pin "1") (pinfunction "1_1") (pintype "passive"))
      (node (ref "C3") (pin "1") (pinfunction "1_1") (pintype "passive"))
      (node (ref "C30") (pin "1") (pinfunction "1_1") (pintype "passive"))
      (node (ref "Q1") (pin "4") (pinfunction "D_4") (pintype "passive"))
      (node (ref "Q3") (pin "4") (pinfunction "D_4") (pintype "passive"))
      (node (ref "TP4") (pin "TP") (pinfunction "TP_TP") (pintype "input"))
    )
    (net (code "6") (name "A0") (class "Default")
      (node (ref "JP2") (pin "3") (pinfunction "3_3") (pintype "passive"))
      (node (ref "U2") (pin "23") (pinfunction "PC0(ADC0)_23") (pintype "bidirectional"))
    )
    (net (code "7") (name "A1") (class "Default")
      (node (ref "JP2") (pin "4") (pinfunction "4_4") (pintype "passive"))
      (node (ref "U2") (pin "24") (pinfunction "PC1(ADC1)_24") (pintype "bidirectional"))
    )
    (net (code "8") (name "A2") (class "Default")
      (node (ref "JP2") (pin "5") (pinfunction "5_5") (pintype "passive"))
      (node (ref "U2") (pin "25") (pinfunction "PC2(ADC2)_25") (pintype "bidirectional"))
    )
    (net (code "9") (name "A3") (class "Default")
      (node (ref "JP2") (pin "6") (pinfunction "6_6") (pintype "passive"))
      (node (ref "U2") (pin "26") (pinfunction "PC3(ADC3)_26") (pintype "bidirectional"))
    )
    (net (code "10") (name "A6") (class "Default")
      (node (ref "C16") (pin "1") (pinfunction "1_1") (pintype "passive"))
      (node (ref "R13") (pin "1") (pinfunction "1_1") (pintype "passive"))
      (node (ref "R14") (pin "2") (pinfunction "2_2") (pintype "passive"))
      (node (ref "U2") (pin "19") (pinfunction "ADC6_19") (pintype "bidirectional"))
    )
    (net (code "11") (name "A7") (class "Default")
      (node (ref "C15") (pin "1") (pinfunction "1_1") (pintype "passive"))
      (node (ref "IC3") (pin "1") (pinfunction "OUT_1") (pintype "output"))
      (node (ref "R15") (pin "2") (pinfunction "2_2") (pintype "passive"))
      (node (ref "U2") (pin "22") (pinfunction "ADC7_22") (pintype "bidirectional"))
    )
    (net (code "12") (name "CHG") (class "Default")
      (node (ref "IC2") (pin "2") (pinfunction "CHG_2") (pintype "output"))
      (node (ref "Q6") (pin "2") (pinfunction "S_2") (pintype "passive"))
    )
    (net (code "13") (name "D2") (class "Default")
      (node (ref "R20") (pin "1") (pinfunction "1_1") (pintype "passive"))
      (node (ref "U2") (pin "32") (pinfunction "PD2(INT0)_32") (pintype "bidirectional"))
    )
    (net (code "14") (name "D3") (class "Default")
      (node (ref "JP3") (pin "1") (pinfunction "1_1") (pintype "passive"))
      (node (ref "U2") (pin "1") (pinfunction "PD3(INT1)_1") (pintype "bidirectional"))
    )
    (net (code "15") (name "D4") (class "Default")
      (node (ref "JP3") (pin "2") (pinfunction "2_2") (pintype "passive"))
      (node (ref "U2") (pin "2") (pinfunction "PD4(XCK/T0)_2") (pintype "bidirectional"))
    )
    (net (code "16") (name "D5") (class "Default")
      (node (ref "JP3") (pin "3") (pinfunction "3_3") (pintype "passive"))
      (node (ref "U2") (pin "9") (pinfunction "PD5(T1)_9") (pintype "bidirectional"))
    )
    (net (code "17") (name "D6") (class "Default")
      (node (ref "JP3") (pin "4") (pinfunction "4_4") (pintype "passive"))
      (node (ref "U2") (pin "10") (pinfunction "PD6(AIN0)_10") (pintype "bidirectional"))
    )
    (net (code "18") (name "D7") (class "Default")
      (node (ref "R19") (pin "1") (pinfunction "1_1") (pintype "passive"))
      (node (ref "U2") (pin "11") (pinfunction "PD7(AIN1)_11") (pintype "bidirectional"))
    )
    (net (code "19") (name "D8") (class "Default")
      (node (ref "IC4") (pin "7") (pinfunction "EN_7") (pintype "input"))
      (node (ref "U2") (pin "12") (pinfunction "PB0(ICP)_12") (pintype "bidirectional"))
    )
    (net (code "20") (name "D9") (class "Default")
      (node (ref "IC4") (pin "8") (pinfunction "IN_8") (pintype "input"))
      (node (ref "R25") (pin "2") (pinfunction "2_2") (pintype "passive"))
      (node (ref "TP1") (pin "TP") (pinfunction "TP_TP") (pintype "input"))
      (node (ref "U2") (pin "13") (pinfunction "PB1(OC1A)_13") (pintype "bidirectional"))
    )
    (net (code "21") (name "D10") (class "Default")
      (node (ref "JP3") (pin "5") (pinfunction "5_5") (pintype "passive"))
      (node (ref "U2") (pin "14") (pinfunction "PB2(SS/OC1B)_14") (pintype "bidirectional"))
    )
    (net (code "22") (name "DSG") (class "Default")
      (node (ref "IC2") (pin "1") (pinfunction "DSG_1") (pintype "output"))
      (node (ref "Q5") (pin "1") (pinfunction "G_1") (pintype "passive"))
      (node (ref "R12") (pin "2") (pinfunction "2_2") (pintype "passive"))
    )
    (net (code "23") (name "DTR") (class "Default")
      (node (ref "C31") (pin "2") (pinfunction "2_2") (pintype "passive"))
      (node (ref "FTDI") (pin "1") (pinfunction "DTR_1") (pintype "passive"))
    )
    (net (code "24") (name "GND") (class "Default")
      (node (ref "BAT") (pin "1") (pinfunction "KL_1") (pintype "passive"))
      (node (ref "C14") (pin "2") (pinfunction "2_2") (pintype "passive"))
      (node (ref "C15") (pin "2") (pinfunction "2_2") (pintype "passive"))
      (node (ref "C16") (pin "2") (pinfunction "2_2") (pintype "passive"))
      (node (ref "C17") (pin "2") (pinfunction "2_2") (pintype "passive"))
      (node (ref "C20") (pin "2") (pinfunction "2_2") (pintype "passive"))
      (node (ref "C21") (pin "2") (pinfunction "2_2") (pintype "passive"))
      (node (ref "C22") (pin "2") (pinfunction "2_2") (pintype "passive"))
      (node (ref "C25") (pin "2") (pinfunction "2_2") (pintype "passive"))
      (node (ref "C26") (pin "2") (pinfunction "2_2") (pintype "passive"))
      (node (ref "C27") (pin "2") (pinfunction "2_2") (pintype "passive"))
      (node (ref "C28") (pin "2") (pinfunction "2_2") (pintype "passive"))
      (node (ref "C29") (pin "2") (pinfunction "2_2") (pintype "passive"))
      (node (ref "C32") (pin "1") (pinfunction "1_1") (pintype "passive"))
      (node (ref "C33") (pin "1") (pinfunction "1_1") (pintype "passive"))
      (node (ref "C8") (pin "1") (pinfunction "1_1") (pintype "passive"))
      (node (ref "C9") (pin "2") (pinfunction "2_2") (pintype "passive"))
      (node (ref "D4") (pin "A") (pinfunction "A_A") (pintype "passive"))
      (node (ref "FTDI") (pin "5") (pinfunction "CTS_5") (pintype "passive"))
      (node (ref "FTDI") (pin "6") (pinfunction "GND_6") (pintype "passive"))
      (node (ref "IC2") (pin "3") (pinfunction "VSS_3") (pintype "power_in"))
      (node (ref "IC3") (pin "2") (pinfunction "V-_2") (pintype "power_in"))
      (node (ref "ICSP") (pin "6") (pinfunction "6_6") (pintype "passive"))
      (node (ref "JP2") (pin "2") (pinfunction "2_2") (pintype "passive"))
      (node (ref "LED2") (pin "C") (pinfunction "C_C") (pintype "passive"))
      (node (ref "Q6") (pin "1") (pinfunction "G_1") (pintype "passive"))
      (node (ref "R11") (pin "1") (pinfunction "1_1") (pintype "passive"))
      (node (ref "R14") (pin "1") (pinfunction "1_1") (pintype "passive"))
      (node (ref "R15") (pin "1") (pinfunction "1_1") (pintype "passive"))
      (node (ref "R23") (pin "1") (pinfunction "1_1") (pintype "passive"))
      (node (ref "R9") (pin "2") (pinfunction "2_2") (pintype "passive"))
      (node (ref "TEMP") (pin "2") (pinfunction "2_2") (pintype "passive"))
      (node (ref "TP2") (pin "TP") (pinfunction "TP_TP") (pintype "input"))
      (node (ref "U1") (pin "2") (pinfunction "GND_2") (pintype "input"))
      (node (ref "U2") (pin "21") (pinfunction "GND_21") (pintype "bidirectional"))
      (node (ref "U2") (pin "3") (pinfunction "GND_3") (pintype "bidirectional"))
      (node (ref "U2") (pin "5") (pinfunction "AGND_5") (pintype "bidirectional"))
      (node (ref "Y1") (pin "2") (pinfunction "2_2") (pintype "passive"))
    )
    (net (code "25") (name "MISO") (class "Default")
      (node (ref "ICSP") (pin "1") (pinfunction "1_1") (pintype "passive"))
      (node (ref "JP3") (pin "7") (pinfunction "7_7") (pintype "passive"))
      (node (ref "U2") (pin "16") (pinfunction "PB4(MISO)_16") (pintype "bidirectional"))
    )
    (net (code "26") (name "MOSI") (class "Default")
      (node (ref "ICSP") (pin "4") (pinfunction "4_4") (pintype "passive"))
      (node (ref "JP3") (pin "6") (pinfunction "6_6") (pintype "passive"))
      (node (ref "U2") (pin "15") (pinfunction "PB3(MOSI/OC2)_15") (pintype "bidirectional"))
    )
    (net (code "27") (name "Net-(BATB-KL)") (class "Default")
      (node (ref "BAT") (pin "2") (pinfunction "KL_2") (pintype "passive"))
      (node (ref "F1") (pin "2A") (pinfunction "2A_2A") (pintype "passive"))
      (node (ref "F1") (pin "2B") (pinfunction "2B_2B") (pintype "passive"))
    )
    (net (code "28") (name "Net-(C5-Pad1)") (class "Default")
      (node (ref "C5") (pin "1") (pinfunction "1_1") (pintype "passive"))
      (node (ref "R1") (pin "1") (pinfunction "1_1") (pintype "passive"))
    )
    (net (code "29") (name "Net-(C7-Pad1)") (class "Default")
      (node (ref "C7") (pin "1") (pinfunction "1_1") (pintype "passive"))
      (node (ref "R21") (pin "1") (pinfunction "1_1") (pintype "passive"))
    )
    (net (code "30") (name "Net-(IC2-ALERT)") (class "Default")
      (node (ref "IC2") (pin "20") (pinfunction "ALERT_20") (pintype "bidirectional"))
      (node (ref "R20") (pin "2") (pinfunction "2_2") (pintype "passive"))
      (node (ref "R23") (pin "2") (pinfunction "2_2") (pintype "passive"))
    )
    (net (code "31") (name "Net-(IC2-BAT)") (class "Default")
      (node (ref "C22") (pin "1") (pinfunction "1_1") (pintype "passive"))
      (node (ref "IC2") (pin "10") (pinfunction "BAT_10") (pintype "power_in"))
      (node (ref "R17") (pin "2") (pinfunction "2_2") (pintype "passive"))
    )
    (net (code "32") (name "Net-(IC2-CAP1)") (class "Default")
      (node (ref "C17") (pin "1") (pinfunction "1_1") (pintype "passive"))
      (node (ref "IC2") (pin "7") (pinfunction "CAP1_7") (pintype "output"))
    )
    (net (code "33") (name "Net-(IC2-TS1)") (class "Default")
      (node (ref "C26") (pin "1") (pinfunction "1_1") (pintype "passive"))
      (node (ref "IC2") (pin "6") (pinfunction "TS1_6") (pintype "input"))
      (node (ref "R19") (pin "2") (pinfunction "2_2") (pintype "passive"))
      (node (ref "TEMP") (pin "1") (pinfunction "1_1") (pintype "passive"))
    )
    (net (code "34") (name "Net-(IC2-VC0)") (class "Default")
      (node (ref "C8") (pin "2") (pinfunction "2_2") (pintype "passive"))
      (node (ref "IC2") (pin "17") (pinfunction "VC0_17") (pintype "input"))
      (node (ref "R2") (pin "2") (pinfunction "2_2") (pintype "passive"))
    )
    (net (code "35") (name "Net-(IC2-VC1)") (class "Default")
      (node (ref "C10") (pin "2") (pinfunction "2_2") (pintype "passive"))
      (node (ref "C9") (pin "1") (pinfunction "1_1") (pintype "passive"))
      (node (ref "IC2") (pin "16") (pinfunction "VC1_16") (pintype "input"))
      (node (ref "R3") (pin "2") (pinfunction "2_2") (pintype "passive"))
    )
    (net (code "36") (name "Net-(IC2-VC2)") (class "Default")
      (node (ref "C10") (pin "1") (pinfunction "1_1") (pintype "passive"))
      (node (ref "C11") (pin "2") (pinfunction "2_2") (pintype "passive"))
      (node (ref "IC2") (pin "15") (pinfunction "VC2_15") (pintype "input"))
      (node (ref "R4") (pin "2") (pinfunction "2_2") (pintype "passive"))
    )
    (net (code "37") (name "Net-(IC2-VC3)") (class "Default")
      (node (ref "C11") (pin "1") (pinfunction "1_1") (pintype "passive"))
      (node (ref "C12") (pin "2") (pinfunction "2_2") (pintype "passive"))
      (node (ref "IC2") (pin "13") (pinfunction "VC4_13") (pintype "input"))
      (node (ref "IC2") (pin "14") (pinfunction "VC3_14") (pintype "input"))
      (node (ref "R5") (pin "2") (pinfunction "2_2") (pintype "passive"))
    )
    (net (code "38") (name "Net-(IC2-VC5)") (class "Default")
      (node (ref "C12") (pin "1") (pinfunction "1_1") (pintype "passive"))
      (node (ref "IC2") (pin "12") (pinfunction "VC5_12") (pintype "input"))
      (node (ref "R6") (pin "2") (pinfunction "2_2") (pintype "passive"))
    )
    (net (code "39") (name "Net-(IC3-IN+)") (class "Default")
      (node (ref "D3") (pin "C") (pinfunction "C_C") (pintype "passive"))
      (node (ref "IC3") (pin "3") (pinfunction "IN+_3") (pintype "input"))
      (node (ref "R13") (pin "2") (pinfunction "2_2") (pintype "passive"))
      (node (ref "R8") (pin "1") (pinfunction "1_1") (pintype "passive"))
      (node (ref "SOLAR") (pin "1") (pinfunction "KL_1") (pintype "passive"))
    )
    (net (code "40") (name "Net-(IC3-IN-)") (class "Default")
      (node (ref "IC3") (pin "4") (pinfunction "IN-_4") (pintype "input"))
      (node (ref "Q3") (pin "3") (pinfunction "S_3") (pintype "passive"))
      (node (ref "R7") (pin "1") (pinfunction "1_1") (pintype "passive"))
      (node (ref "R8") (pin "2") (pinfunction "2_2") (pintype "passive"))
    )
    (net (code "41") (name "Net-(IC4-HB)") (class "Default")
      (node (ref "D1") (pin "C") (pinfunction "C_C") (pintype "passive"))
      (node (ref "IC4") (pin "2") (pinfunction "HB_2") (pintype "input"))
      (node (ref "R1") (pin "2") (pinfunction "2_2") (pintype "passive"))
    )
    (net (code "42") (name "Net-(IC4-HO)") (class "Default")
      (node (ref "D2") (pin "A") (pinfunction "A_A") (pintype "passive"))
      (node (ref "IC4") (pin "3") (pinfunction "HO_3") (pintype "output"))
      (node (ref "Q1") (pin "1") (pinfunction "G_1") (pintype "passive"))
    )
    (net (code "43") (name "Net-(IC4-HS)") (class "Default")
      (node (ref "C5") (pin "2") (pinfunction "2_2") (pintype "passive"))
      (node (ref "IC4") (pin "4") (pinfunction "HS_4") (pintype "input"))
      (node (ref "L1") (pin "2") (pinfunction "2_2") (pintype "bidirectional"))
      (node (ref "Q1") (pin "3") (pinfunction "S_3") (pintype "passive"))
      (node (ref "Q2") (pin "4") (pinfunction "D_4") (pintype "passive"))
      (node (ref "R21") (pin "2") (pinfunction "2_2") (pintype "passive"))
    )
    (net (code "44") (name "Net-(IC4-LO)") (class "Default")
      (node (ref "IC4") (pin "10") (pinfunction "LO_10") (pintype "output"))
      (node (ref "Q2") (pin "1") (pinfunction "G_1") (pintype "passive"))
    )
    (net (code "45") (name "Net-(IC4-RDT)") (class "Default")
      (node (ref "IC4") (pin "6") (pinfunction "RDT_6") (pintype "input"))
      (node (ref "R22") (pin "2") (pinfunction "2_2") (pintype "passive"))
    )
    (net (code "46") (name "Net-(LED1-PadA)") (class "Default")
      (node (ref "LED1") (pin "A") (pinfunction "A_A") (pintype "passive"))
      (node (ref "R25") (pin "1") (pinfunction "1_1") (pintype "passive"))
    )
    (net (code "47") (name "Net-(LED2-PadA)") (class "Default")
      (node (ref "LED2") (pin "A") (pinfunction "A_A") (pintype "passive"))
      (node (ref "R47") (pin "2") (pinfunction "2_2") (pintype "passive"))
    )
    (net (code "48") (name "Net-(Q3-G)") (class "Default")
      (node (ref "D2") (pin "C") (pinfunction "C_C") (pintype "passive"))
      (node (ref "Q3") (pin "1") (pinfunction "G_1") (pintype "passive"))
      (node (ref "R7") (pin "2") (pinfunction "2_2") (pintype "passive"))
    )
    (net (code "49") (name "Net-(Q4-D)") (class "Default")
      (node (ref "C23") (pin "2") (pinfunction "2_2") (pintype "passive"))
      (node (ref "Q4") (pin "4") (pinfunction "D_4") (pintype "passive"))
      (node (ref "Q5") (pin "4") (pinfunction "D_4") (pintype "passive"))
    )
    (net (code "50") (name "Net-(Q4-G)") (class "Default")
      (node (ref "C23") (pin "1") (pinfunction "1_1") (pintype "passive"))
      (node (ref "D5") (pin "C") (pinfunction "C_C") (pintype "passive"))
      (node (ref "Q4") (pin "1") (pinfunction "G_1") (pintype "passive"))
      (node (ref "R16") (pin "2") (pinfunction "2_2") (pintype "passive"))
      (node (ref "R18") (pin "1") (pinfunction "1_1") (pintype "passive"))
    )
    (net (code "51") (name "Net-(Q5-S)") (class "Default")
      (node (ref "Q5") (pin "3") (pinfunction "S_3") (pintype "passive"))
      (node (ref "R10") (pin "1") (pinfunction "1_1") (pintype "passive"))
      (node (ref "R12") (pin "1") (pinfunction "1_1") (pintype "passive"))
      (node (ref "R24") (pin "1") (pinfunction "1_1") (pintype "passive"))
      (node (ref "R9") (pin "1") (pinfunction "1_1") (pintype "passive"))
    )
    (net (code "52") (name "Net-(Q6-D)") (class "Default")
      (node (ref "D5") (pin "A") (pinfunction "A_A") (pintype "passive"))
      (node (ref "Q6") (pin "3") (pinfunction "D_3") (pintype "passive"))
      (node (ref "R18") (pin "2") (pinfunction "2_2") (pintype "passive"))
    )
    (net (code "53") (name "Net-(U2-PB6(XTAL1{slash}TOSC1))") (class "Default")
      (node (ref "U2") (pin "7") (pinfunction "PB6(XTAL1/TOSC1)_7") (pintype "bidirectional"))
      (node (ref "Y1") (pin "1") (pinfunction "1_1") (pintype "passive"))
    )
    (net (code "54") (name "Net-(U2-PB7(XTAL2{slash}TOSC2))") (class "Default")
      (node (ref "U2") (pin "8") (pinfunction "PB7(XTAL2/TOSC2)_8") (pintype "bidirectional"))
      (node (ref "Y1") (pin "3") (pinfunction "3_3") (pintype "passive"))
    )
    (net (code "55") (name "Net-(X1A-1)") (class "Default")
      (node (ref "R2") (pin "1") (pinfunction "1_1") (pintype "passive"))
      (node (ref "X1") (pin "P$1") (pinfunction "1_P$1") (pintype "passive"))
    )
    (net (code "56") (name "Net-(X1B-1)") (class "Default")
      (node (ref "R3") (pin "1") (pinfunction "1_1") (pintype "passive"))
      (node (ref "X1") (pin "P$2") (pinfunction "1_P$2") (pintype "passive"))
    )
    (net (code "57") (name "Net-(X1C-1)") (class "Default")
      (node (ref "R4") (pin "1") (pinfunction "1_1") (pintype "passive"))
      (node (ref "X1") (pin "P$3") (pinfunction "1_P$3") (pintype "passive"))
    )
    (net (code "58") (name "Net-(X1D-1)") (class "Default")
      (node (ref "R5") (pin "1") (pinfunction "1_1") (pintype "passive"))
      (node (ref "X1") (pin "P$4") (pinfunction "1_P$4") (pintype "passive"))
    )
    (net (code "59") (name "Net-(X1E-1)") (class "Default")
      (node (ref "R6") (pin "1") (pinfunction "1_1") (pintype "passive"))
      (node (ref "X1") (pin "P$5") (pinfunction "1_P$5") (pintype "passive"))
    )
    (net (code "60") (name "PGND") (class "Default")
      (node (ref "C1") (pin "-") (pinfunction "-_-") (pintype "passive"))
      (node (ref "C18") (pin "-") (pinfunction "-_-") (pintype "passive"))
      (node (ref "C19") (pin "2") (pinfunction "2_2") (pintype "passive"))
      (node (ref "C2") (pin "2") (pinfunction "2_2") (pintype "passive"))
      (node (ref "C24") (pin "2") (pinfunction "2_2") (pintype "passive"))
      (node (ref "C3") (pin "2") (pinfunction "2_2") (pintype "passive"))
      (node (ref "C30") (pin "2") (pinfunction "2_2") (pintype "passive"))
      (node (ref "C4") (pin "-") (pinfunction "-_-") (pintype "passive"))
      (node (ref "C6") (pin "2") (pinfunction "2_2") (pintype "passive"))
      (node (ref "C7") (pin "2") (pinfunction "2_2") (pintype "passive"))
      (node (ref "D3") (pin "A") (pinfunction "A_A") (pintype "passive"))
      (node (ref "IC4") (pin "9") (pinfunction "VSS_9") (pintype "power_in"))
      (node (ref "LED1") (pin "K") (pinfunction "C_K") (pintype "passive"))
      (node (ref "LOAD") (pin "1") (pinfunction "KL_1") (pintype "passive"))
      (node (ref "Q2") (pin "3") (pinfunction "S_3") (pintype "passive"))
      (node (ref "Q4") (pin "3") (pinfunction "S_3") (pintype "passive"))
      (node (ref "R16") (pin "1") (pinfunction "1_1") (pintype "passive"))
      (node (ref "R22") (pin "1") (pinfunction "1_1") (pintype "passive"))
      (node (ref "R24") (pin "2") (pinfunction "2_2") (pintype "passive"))
      (node (ref "SOLAR") (pin "2") (pinfunction "KL_2") (pintype "passive"))
      (node (ref "TP3") (pin "TP") (pinfunction "TP_TP") (pintype "input"))
    )
    (net (code "61") (name "RESET") (class "Default")
      (node (ref "C31") (pin "1") (pinfunction "1_1") (pintype "passive"))
      (node (ref "ICSP") (pin "5") (pinfunction "5_5") (pintype "passive"))
      (node (ref "R46") (pin "1") (pinfunction "1_1") (pintype "passive"))
      (node (ref "U2") (pin "29") (pinfunction "PC6(/RESET)_29") (pintype "bidirectional"))
    )
    (net (code "62") (name "RXI") (class "Default")
      (node (ref "FTDI") (pin "3") (pinfunction "TXO_3") (pintype "passive"))
      (node (ref "U2") (pin "30") (pinfunction "PD0(RXD)_30") (pintype "bidirectional"))
    )
    (net (code "63") (name "SCK") (class "Default")
      (node (ref "ICSP") (pin "3") (pinfunction "3_3") (pintype "passive"))
      (node (ref "JP3") (pin "8") (pinfunction "8_8") (pintype "passive"))
      (node (ref "R47") (pin "1") (pinfunction "1_1") (pintype "passive"))
      (node (ref "U2") (pin "17") (pinfunction "PB5(SCK)_17") (pintype "bidirectional"))
    )
    (net (code "64") (name "SCL") (class "Default")
      (node (ref "IC2") (pin "5") (pinfunction "SCL_5") (pintype "input"))
      (node (ref "JP2") (pin "8") (pinfunction "8_8") (pintype "passive"))
      (node (ref "R48") (pin "1") (pinfunction "1_1") (pintype "passive"))
      (node (ref "U2") (pin "28") (pinfunction "PC5(ADC5/SCL)_28") (pintype "bidirectional"))
    )
    (net (code "65") (name "SDA") (class "Default")
      (node (ref "IC2") (pin "4") (pinfunction "SDA_4") (pintype "bidirectional"))
      (node (ref "JP2") (pin "7") (pinfunction "7_7") (pintype "passive"))
      (node (ref "R45") (pin "1") (pinfunction "1_1") (pintype "passive"))
      (node (ref "U2") (pin "27") (pinfunction "PC4(ADC4/SDA)_27") (pintype "bidirectional"))
    )
    (net (code "66") (name "SRN") (class "Default")
      (node (ref "C13") (pin "1") (pinfunction "1_1") (pintype "passive"))
      (node (ref "C27") (pin "1") (pinfunction "1_1") (pintype "passive"))
      (node (ref "IC2") (pin "19") (pinfunction "SRN_19") (pintype "input"))
      (node (ref "R10") (pin "2") (pinfunction "2_2") (pintype "passive"))
    )
    (net (code "67") (name "SRP") (class "Default")
      (node (ref "C13") (pin "2") (pinfunction "2_2") (pintype "passive"))
      (node (ref "C28") (pin "1") (pinfunction "1_1") (pintype "passive"))
      (node (ref "IC2") (pin "18") (pinfunction "SRP_18") (pintype "input"))
      (node (ref "R11") (pin "2") (pinfunction "2_2") (pintype "passive"))
    )
    (net (code "68") (name "TXO") (class "Default")
      (node (ref "FTDI") (pin "2") (pinfunction "RXI_2") (pintype "passive"))
      (node (ref "U2") (pin "31") (pinfunction "PD1(TXD)_31") (pintype "bidirectional"))
    )
    (net (code "69") (name "unconnected-(IC2-NC-Pad11)") (class "Default")
      (node (ref "IC2") (pin "11") (pinfunction "NC_11") (pintype "no_connect"))
    )
    (net (code "70") (name "unconnected-(U1-BP-Pad4)") (class "Default")
      (node (ref "U1") (pin "4") (pinfunction "BP_4") (pintype "input"))
    )
  )
)
